# MMIC_LNA.net
KiCad netlist of a schematic drawn in EAGLE
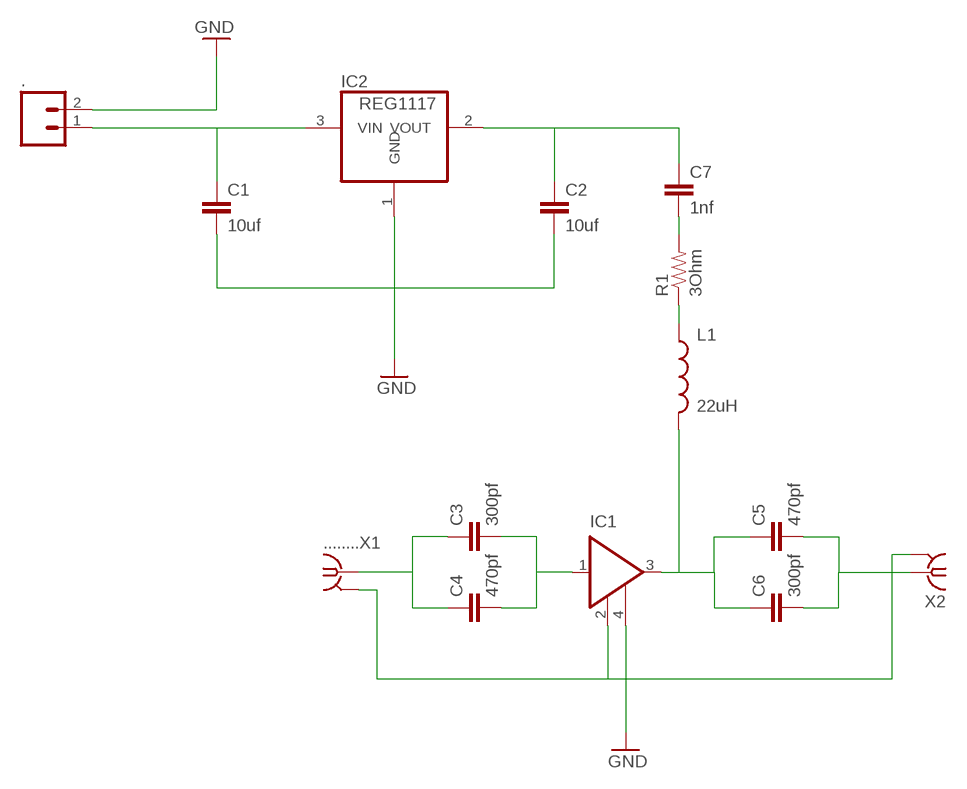
[diagram p0: schematic, sheet 1]

(export (version "E")
  (design (tool "Eeschema 10.0.6"))
  (components
    (comp (ref ".")
      (value "M02LOCK_LONGPADS")
      (footprint "eagle-import:1X02_LOCK_LONGPADS")
      (libsource (lib "eagle-import") (part "M02LOCK_LONGPADS"))
    )
    (comp (ref "........X1")
      (value "BU-SMA-V")
      (footprint "eagle-import:BU-SMA-V")
      (libsource (lib "eagle-import") (part "BU-SMA-V"))
    )
    (comp (ref "C1")
      (value "10uf")
      (footprint "eagle-import:0603-CAP")
      (libsource (lib "eagle-import") (part "CAP0603-CAP"))
    )
    (comp (ref "C2")
      (value "10uf")
      (footprint "eagle-import:0603-CAP")
      (libsource (lib "eagle-import") (part "CAP0603-CAP"))
    )
    (comp (ref "C3")
      (value "300pf")
      (footprint "eagle-import:0603-CAP")
      (libsource (lib "eagle-import") (part "CAP0603-CAP"))
    )
    (comp (ref "C4")
      (value "470pf")
      (footprint "eagle-import:0603-CAP")
      (libsource (lib "eagle-import") (part "CAP0603-CAP"))
    )
    (comp (ref "C5")
      (value "470pf")
      (footprint "eagle-import:0603-CAP")
      (libsource (lib "eagle-import") (part "CAP0603-CAP"))
    )
    (comp (ref "C6")
      (value "300pf")
      (footprint "eagle-import:0603-CAP")
      (libsource (lib "eagle-import") (part "CAP0603-CAP"))
    )
    (comp (ref "C7")
      (value "1nf")
      (footprint "eagle-import:0603-CAP")
      (libsource (lib "eagle-import") (part "CAP0603-CAP"))
    )
    (comp (ref "IC1")
      (value "ERA-3SM")
      (footprint "eagle-import:WW")
      (libsource (lib "eagle-import") (part "ERA-SM3"))
    )
    (comp (ref "IC2")
      (value "REG1117")
      (footprint "eagle-import:SOT223")
      (libsource (lib "eagle-import") (part "REG1117"))
    )
    (comp (ref "L1")
      (value "22uH")
      (footprint "eagle-import:0603")
      (libsource (lib "eagle-import") (part "INDUCTOR0603"))
    )
    (comp (ref "R1")
      (value "3Ohm")
      (footprint "eagle-import:0603-RES")
      (libsource (lib "eagle-import") (part "RESISTOR0603-RES"))
    )
    (comp (ref "X2")
      (value "BU-SMA-V")
      (footprint "eagle-import:BU-SMA-V")
      (libsource (lib "eagle-import") (part "BU-SMA-V"))
    )
  )
  (nets
    (net (code "1") (name "GND") (class "Default")
      (node (ref ".") (pin "2") (pinfunction "2_2") (pintype "passive"))
      (node (ref "........X1") (pin "2") (pinfunction "2_2") (pintype "passive"))
      (node (ref "........X1") (pin "3") (pinfunction "2_3") (pintype "passive"))
      (node (ref "........X1") (pin "4") (pinfunction "2_4") (pintype "passive"))
      (node (ref "........X1") (pin "5") (pinfunction "2_5") (pintype "passive"))
      (node (ref "C1") (pin "2") (pinfunction "2_2") (pintype "passive"))
      (node (ref "C2") (pin "2") (pinfunction "2_2") (pintype "passive"))
      (node (ref "IC1") (pin "2") (pinfunction "GND_2") (pintype "power_in"))
      (node (ref "IC1") (pin "4") (pinfunction "GND_4") (pintype "power_in"))
      (node (ref "IC2") (pin "1") (pinfunction "GND_1") (pintype "power_in"))
      (node (ref "X2") (pin "2") (pinfunction "2_2") (pintype "passive"))
      (node (ref "X2") (pin "3") (pinfunction "2_3") (pintype "passive"))
      (node (ref "X2") (pin "4") (pinfunction "2_4") (pintype "passive"))
      (node (ref "X2") (pin "5") (pinfunction "2_5") (pintype "passive"))
    )
    (net (code "2") (name "Net-(........X1-Pad1)") (class "Default")
      (node (ref "........X1") (pin "1") (pinfunction "1_1") (pintype "passive"))
      (node (ref "C3") (pin "1") (pinfunction "1_1") (pintype "passive"))
      (node (ref "C4") (pin "1") (pinfunction "1_1") (pintype "passive"))
    )
    (net (code "3") (name "Net-(C5-Pad2)") (class "Default")
      (node (ref "C5") (pin "2") (pinfunction "2_2") (pintype "passive"))
      (node (ref "C6") (pin "2") (pinfunction "2_2") (pintype "passive"))
      (node (ref "X2") (pin "1") (pinfunction "1_1") (pintype "passive"))
    )
    (net (code "4") (name "Net-(C7-Pad2)") (class "Default")
      (node (ref "C7") (pin "2") (pinfunction "2_2") (pintype "passive"))
      (node (ref "R1") (pin "2") (pinfunction "2_2") (pintype "passive"))
    )
    (net (code "5") (name "Net-(IC1-RFIN)") (class "Default")
      (node (ref "C3") (pin "2") (pinfunction "2_2") (pintype "passive"))
      (node (ref "C4") (pin "2") (pinfunction "2_2") (pintype "passive"))
      (node (ref "IC1") (pin "1") (pinfunction "RFIN_1") (pintype "input"))
    )
    (net (code "6") (name "Net-(IC1-RFOUT{slash}DCIN)") (class "Default")
      (node (ref "C5") (pin "1") (pinfunction "1_1") (pintype "passive"))
      (node (ref "C6") (pin "1") (pinfunction "1_1") (pintype "passive"))
      (node (ref "IC1") (pin "3") (pinfunction "RFOUT/DCIN_3") (pintype "output"))
      (node (ref "L1") (pin "2") (pinfunction "2_2") (pintype "passive"))
    )
    (net (code "7") (name "Net-(IC2-VIN)") (class "Default")
      (node (ref ".") (pin "1") (pinfunction "1_1") (pintype "passive"))
      (node (ref "C1") (pin "1") (pinfunction "1_1") (pintype "passive"))
      (node (ref "IC2") (pin "3") (pinfunction "VIN_3") (pintype "input"))
    )
    (net (code "8") (name "Net-(IC2-VOUT)") (class "Default")
      (node (ref "C2") (pin "1") (pinfunction "1_1") (pintype "passive"))
      (node (ref "C7") (pin "1") (pinfunction "1_1") (pintype "passive"))
      (node (ref "IC2") (pin "2") (pinfunction "VOUT_2") (pintype "output"))
    )
    (net (code "9") (name "Net-(L1-Pad1)") (class "Default")
      (node (ref "L1") (pin "1") (pinfunction "1_1") (pintype "passive"))
      (node (ref "R1") (pin "1") (pinfunction "1_1") (pintype "passive"))
    )
  )
)
